# shock.net
KiCad netlist of a schematic drawn in Altium Designer
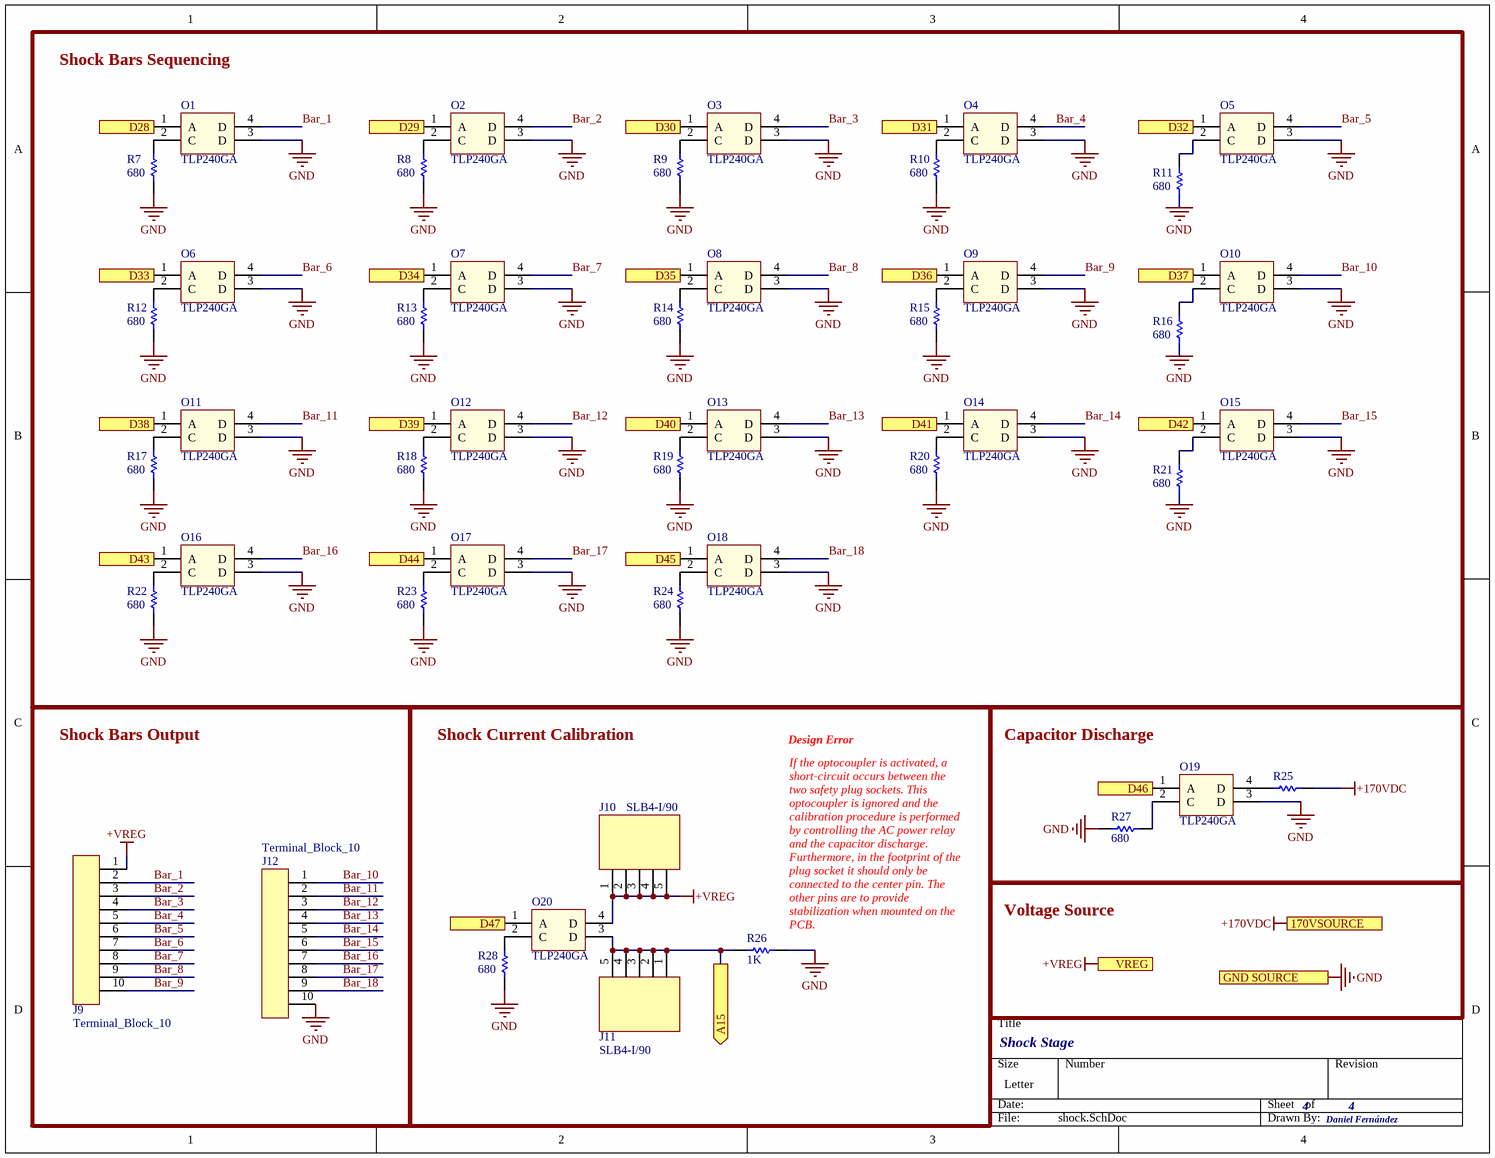
[diagram p0: shock.SchDoc]

(export (version "E")
  (design (tool "Eeschema 10.0.6"))
  (components
    (comp (ref "J9")
      (value "Terminal_Block_10")
      (footprint "Terminal_Block_10")
      (libsource (lib "Components_Schematics") (part "Terminal_Block_10"))
    )
    (comp (ref "J10") (value "SLB4-I/90") (footprint "SLB4-I/90") (libsource (lib "") (part "SLB4-I/90_1")))
    (comp (ref "J11")
      (value "SLB4-I/90")
      (footprint "SLB4-I/90")
      (libsource (lib "Components_Schematics") (part "SLB4-I/90"))
    )
    (comp (ref "J12")
      (value "Terminal_Block_10")
      (footprint "Terminal_Block_10")
      (libsource (lib "Components_Schematics") (part "Terminal_Block_10"))
    )
    (comp (ref "O1")
      (value "TLP240GA")
      (footprint "TLP240GA")
      (description "Photorelay")
      (libsource (lib "Components_Schematics") (part "TLP240GA"))
    )
    (comp (ref "O2")
      (value "TLP240GA")
      (footprint "TLP240GA")
      (description "Photorelay")
      (libsource (lib "Components_Schematics") (part "TLP240GA"))
    )
    (comp (ref "O3")
      (value "TLP240GA")
      (footprint "TLP240GA")
      (description "Photorelay")
      (libsource (lib "Components_Schematics") (part "TLP240GA"))
    )
    (comp (ref "O4")
      (value "TLP240GA")
      (footprint "TLP240GA")
      (description "Photorelay")
      (libsource (lib "Components_Schematics") (part "TLP240GA"))
    )
    (comp (ref "O5")
      (value "TLP240GA")
      (footprint "TLP240GA")
      (description "Photorelay")
      (libsource (lib "Components_Schematics") (part "TLP240GA"))
    )
    (comp (ref "O6")
      (value "TLP240GA")
      (footprint "TLP240GA")
      (description "Photorelay")
      (libsource (lib "Components_Schematics") (part "TLP240GA"))
    )
    (comp (ref "O7")
      (value "TLP240GA")
      (footprint "TLP240GA")
      (description "Photorelay")
      (libsource (lib "Components_Schematics") (part "TLP240GA"))
    )
    (comp (ref "O8")
      (value "TLP240GA")
      (footprint "TLP240GA")
      (description "Photorelay")
      (libsource (lib "Components_Schematics") (part "TLP240GA"))
    )
    (comp (ref "O9")
      (value "TLP240GA")
      (footprint "TLP240GA")
      (description "Photorelay")
      (libsource (lib "Components_Schematics") (part "TLP240GA"))
    )
    (comp (ref "O10")
      (value "TLP240GA")
      (footprint "TLP240GA")
      (description "Photorelay")
      (libsource (lib "Components_Schematics") (part "TLP240GA"))
    )
    (comp (ref "O11")
      (value "TLP240GA")
      (footprint "TLP240GA")
      (description "Photorelay")
      (libsource (lib "Components_Schematics") (part "TLP240GA"))
    )
    (comp (ref "O12")
      (value "TLP240GA")
      (footprint "TLP240GA")
      (description "Photorelay")
      (libsource (lib "Components_Schematics") (part "TLP240GA"))
    )
    (comp (ref "O13")
      (value "TLP240GA")
      (footprint "TLP240GA")
      (description "Photorelay")
      (libsource (lib "Components_Schematics") (part "TLP240GA"))
    )
    (comp (ref "O14")
      (value "TLP240GA")
      (footprint "TLP240GA")
      (description "Photorelay")
      (libsource (lib "Components_Schematics") (part "TLP240GA"))
    )
    (comp (ref "O15")
      (value "TLP240GA")
      (footprint "TLP240GA")
      (description "Photorelay")
      (libsource (lib "Components_Schematics") (part "TLP240GA"))
    )
    (comp (ref "O16")
      (value "TLP240GA")
      (footprint "TLP240GA")
      (description "Photorelay")
      (libsource (lib "Components_Schematics") (part "TLP240GA"))
    )
    (comp (ref "O17")
      (value "TLP240GA")
      (footprint "TLP240GA")
      (description "Photorelay")
      (libsource (lib "Components_Schematics") (part "TLP240GA"))
    )
    (comp (ref "O18")
      (value "TLP240GA")
      (footprint "TLP240GA")
      (description "Photorelay")
      (libsource (lib "Components_Schematics") (part "TLP240GA"))
    )
    (comp (ref "O19")
      (value "TLP240GA")
      (footprint "TLP240GA")
      (description "Photorelay")
      (libsource (lib "Components_Schematics") (part "TLP240GA"))
    )
    (comp (ref "O20")
      (value "TLP240GA")
      (footprint "TLP240GA")
      (description "Photorelay")
      (libsource (lib "Components_Schematics") (part "TLP240GA"))
    )
    (comp (ref "R7")
      (value "680")
      (footprint "RESISTOR")
      (description "Resistor_Axial")
      (fields (field (name "PUBLISHER") "Altium Limited"))
      (libsource (lib "PERCRO_schematic") (part "Resistor_Axial"))
    )
    (comp (ref "R8")
      (value "680")
      (footprint "RESISTOR")
      (description "Resistor_Axial")
      (fields (field (name "PUBLISHER") "Altium Limited"))
      (libsource (lib "PERCRO_schematic") (part "Resistor_Axial"))
    )
    (comp (ref "R9")
      (value "680")
      (footprint "RESISTOR")
      (description "Resistor_Axial")
      (fields (field (name "PUBLISHER") "Altium Limited"))
      (libsource (lib "PERCRO_schematic") (part "Resistor_Axial"))
    )
    (comp (ref "R10")
      (value "680")
      (footprint "RESISTOR")
      (description "Resistor_Axial")
      (fields (field (name "PUBLISHER") "Altium Limited"))
      (libsource (lib "PERCRO_schematic") (part "Resistor_Axial"))
    )
    (comp (ref "R11")
      (value "680")
      (footprint "RESISTOR")
      (description "Resistor_Axial")
      (fields (field (name "PUBLISHER") "Altium Limited"))
      (libsource (lib "PERCRO_schematic") (part "Resistor_Axial"))
    )
    (comp (ref "R12")
      (value "680")
      (footprint "RESISTOR")
      (description "Resistor_Axial")
      (fields (field (name "PUBLISHER") "Altium Limited"))
      (libsource (lib "PERCRO_schematic") (part "Resistor_Axial"))
    )
    (comp (ref "R13")
      (value "680")
      (footprint "RESISTOR")
      (description "Resistor_Axial")
      (fields (field (name "PUBLISHER") "Altium Limited"))
      (libsource (lib "PERCRO_schematic") (part "Resistor_Axial"))
    )
    (comp (ref "R14")
      (value "680")
      (footprint "RESISTOR")
      (description "Resistor_Axial")
      (fields (field (name "PUBLISHER") "Altium Limited"))
      (libsource (lib "PERCRO_schematic") (part "Resistor_Axial"))
    )
    (comp (ref "R15")
      (value "680")
      (footprint "RESISTOR")
      (description "Resistor_Axial")
      (fields (field (name "PUBLISHER") "Altium Limited"))
      (libsource (lib "PERCRO_schematic") (part "Resistor_Axial"))
    )
    (comp (ref "R16")
      (value "680")
      (footprint "RESISTOR")
      (description "Resistor_Axial")
      (fields (field (name "PUBLISHER") "Altium Limited"))
      (libsource (lib "PERCRO_schematic") (part "Resistor_Axial"))
    )
    (comp (ref "R17")
      (value "680")
      (footprint "RESISTOR")
      (description "Resistor_Axial")
      (fields (field (name "PUBLISHER") "Altium Limited"))
      (libsource (lib "PERCRO_schematic") (part "Resistor_Axial"))
    )
    (comp (ref "R18")
      (value "680")
      (footprint "RESISTOR")
      (description "Resistor_Axial")
      (fields (field (name "PUBLISHER") "Altium Limited"))
      (libsource (lib "PERCRO_schematic") (part "Resistor_Axial"))
    )
    (comp (ref "R19")
      (value "680")
      (footprint "RESISTOR")
      (description "Resistor_Axial")
      (fields (field (name "PUBLISHER") "Altium Limited"))
      (libsource (lib "PERCRO_schematic") (part "Resistor_Axial"))
    )
    (comp (ref "R20")
      (value "680")
      (footprint "RESISTOR")
      (description "Resistor_Axial")
      (fields (field (name "PUBLISHER") "Altium Limited"))
      (libsource (lib "PERCRO_schematic") (part "Resistor_Axial"))
    )
    (comp (ref "R21")
      (value "680")
      (footprint "RESISTOR")
      (description "Resistor_Axial")
      (fields (field (name "PUBLISHER") "Altium Limited"))
      (libsource (lib "PERCRO_schematic") (part "Resistor_Axial"))
    )
    (comp (ref "R22")
      (value "680")
      (footprint "RESISTOR")
      (description "Resistor_Axial")
      (fields (field (name "PUBLISHER") "Altium Limited"))
      (libsource (lib "PERCRO_schematic") (part "Resistor_Axial"))
    )
    (comp (ref "R23")
      (value "680")
      (footprint "RESISTOR")
      (description "Resistor_Axial")
      (fields (field (name "PUBLISHER") "Altium Limited"))
      (libsource (lib "PERCRO_schematic") (part "Resistor_Axial"))
    )
    (comp (ref "R24")
      (value "680")
      (footprint "RESISTOR")
      (description "Resistor_Axial")
      (fields (field (name "PUBLISHER") "Altium Limited"))
      (libsource (lib "PERCRO_schematic") (part "Resistor_Axial"))
    )
    (comp (ref "R25")
      (value "Ceramic Resistor")
      (footprint "AXIAL_CERAMIC_RESISTOR")
      (libsource (lib "Components_Schematics") (part "AXIAL_CERAMIC_RESISTOR"))
    )
    (comp (ref "R26")
      (value "1K")
      (footprint "RESISTOR")
      (description "Resistor_Axial")
      (fields (field (name "PUBLISHER") "Altium Limited"))
      (libsource (lib "PERCRO_schematic") (part "Resistor_Axial"))
    )
    (comp (ref "R27")
      (value "680")
      (footprint "RESISTOR")
      (description "Resistor_Axial")
      (fields (field (name "PUBLISHER") "Altium Limited"))
      (libsource (lib "PERCRO_schematic") (part "Resistor_Axial"))
    )
    (comp (ref "R28")
      (value "680")
      (footprint "RESISTOR")
      (description "Resistor_Axial")
      (fields (field (name "PUBLISHER") "Altium Limited"))
      (libsource (lib "PERCRO_schematic") (part "Resistor_Axial"))
    )
  )
  (nets
    (net (code "1") (name "+170VDC") (class "Default")
      (node (ref "R25") (pin "2") (pinfunction "2_2") (pintype "passive"))
    )
    (net (code "2") (name "+VREG") (class "Default")
      (node (ref "J10") (pin "1") (pinfunction "1_1") (pintype "passive"))
      (node (ref "J10") (pin "2") (pinfunction "Vin_2") (pintype "passive"))
      (node (ref "J10") (pin "3") (pinfunction "Vin_3") (pintype "passive"))
      (node (ref "J10") (pin "4") (pinfunction "Vin_4") (pintype "passive"))
      (node (ref "J10") (pin "5") (pinfunction "Vin_5") (pintype "passive"))
      (node (ref "J9") (pin "1") (pinfunction "1_1") (pintype "passive"))
      (node (ref "O20") (pin "4") (pinfunction "D_4") (pintype "passive"))
    )
    (net (code "3") (name "/A15") (class "Default")
      (node (ref "J11") (pin "1") (pinfunction "1_1") (pintype "passive"))
      (node (ref "J11") (pin "2") (pinfunction "Vin_2") (pintype "passive"))
      (node (ref "J11") (pin "3") (pinfunction "Vin_3") (pintype "passive"))
      (node (ref "J11") (pin "4") (pinfunction "Vin_4") (pintype "passive"))
      (node (ref "J11") (pin "5") (pinfunction "Vin_5") (pintype "passive"))
      (node (ref "O20") (pin "3") (pinfunction "D_3") (pintype "passive"))
      (node (ref "R26") (pin "1") (pinfunction "1_1") (pintype "passive"))
    )
    (net (code "4") (name "/Bar_1") (class "Default")
      (node (ref "J9") (pin "2") (pinfunction "2_2") (pintype "passive"))
      (node (ref "O1") (pin "4") (pinfunction "D_4") (pintype "passive"))
    )
    (net (code "5") (name "/Bar_2") (class "Default")
      (node (ref "J9") (pin "3") (pinfunction "3_3") (pintype "passive"))
      (node (ref "O2") (pin "4") (pinfunction "D_4") (pintype "passive"))
    )
    (net (code "6") (name "/Bar_3") (class "Default")
      (node (ref "J9") (pin "4") (pinfunction "4_4") (pintype "passive"))
      (node (ref "O3") (pin "4") (pinfunction "D_4") (pintype "passive"))
    )
    (net (code "7") (name "/Bar_4") (class "Default")
      (node (ref "J9") (pin "5") (pinfunction "5_5") (pintype "passive"))
      (node (ref "O4") (pin "4") (pinfunction "D_4") (pintype "passive"))
    )
    (net (code "8") (name "/Bar_5") (class "Default")
      (node (ref "J9") (pin "6") (pinfunction "6_6") (pintype "passive"))
      (node (ref "O5") (pin "4") (pinfunction "D_4") (pintype "passive"))
    )
    (net (code "9") (name "/Bar_6") (class "Default")
      (node (ref "J9") (pin "7") (pinfunction "7_7") (pintype "passive"))
      (node (ref "O6") (pin "4") (pinfunction "D_4") (pintype "passive"))
    )
    (net (code "10") (name "/Bar_7") (class "Default")
      (node (ref "J9") (pin "8") (pinfunction "8_8") (pintype "passive"))
      (node (ref "O7") (pin "4") (pinfunction "D_4") (pintype "passive"))
    )
    (net (code "11") (name "/Bar_8") (class "Default")
      (node (ref "J9") (pin "9") (pinfunction "9_9") (pintype "passive"))
      (node (ref "O8") (pin "4") (pinfunction "D_4") (pintype "passive"))
    )
    (net (code "12") (name "/Bar_9") (class "Default")
      (node (ref "J9") (pin "10") (pinfunction "10_10") (pintype "passive"))
      (node (ref "O9") (pin "4") (pinfunction "D_4") (pintype "passive"))
    )
    (net (code "13") (name "/Bar_10") (class "Default")
      (node (ref "J12") (pin "1") (pinfunction "1_1") (pintype "passive"))
      (node (ref "O10") (pin "4") (pinfunction "D_4") (pintype "passive"))
    )
    (net (code "14") (name "/Bar_11") (class "Default")
      (node (ref "J12") (pin "2") (pinfunction "2_2") (pintype "passive"))
      (node (ref "O11") (pin "4") (pinfunction "D_4") (pintype "passive"))
    )
    (net (code "15") (name "/Bar_12") (class "Default")
      (node (ref "J12") (pin "3") (pinfunction "3_3") (pintype "passive"))
      (node (ref "O12") (pin "4") (pinfunction "D_4") (pintype "passive"))
    )
    (net (code "16") (name "/Bar_13") (class "Default")
      (node (ref "J12") (pin "4") (pinfunction "4_4") (pintype "passive"))
      (node (ref "O13") (pin "4") (pinfunction "D_4") (pintype "passive"))
    )
    (net (code "17") (name "/Bar_14") (class "Default")
      (node (ref "J12") (pin "5") (pinfunction "5_5") (pintype "passive"))
      (node (ref "O14") (pin "4") (pinfunction "D_4") (pintype "passive"))
    )
    (net (code "18") (name "/Bar_15") (class "Default")
      (node (ref "J12") (pin "6") (pinfunction "6_6") (pintype "passive"))
      (node (ref "O15") (pin "4") (pinfunction "D_4") (pintype "passive"))
    )
    (net (code "19") (name "/Bar_16") (class "Default")
      (node (ref "J12") (pin "7") (pinfunction "7_7") (pintype "passive"))
      (node (ref "O16") (pin "4") (pinfunction "D_4") (pintype "passive"))
    )
    (net (code "20") (name "/Bar_17") (class "Default")
      (node (ref "J12") (pin "8") (pinfunction "8_8") (pintype "passive"))
      (node (ref "O17") (pin "4") (pinfunction "D_4") (pintype "passive"))
    )
    (net (code "21") (name "/Bar_18") (class "Default")
      (node (ref "J12") (pin "9") (pinfunction "9_9") (pintype "passive"))
      (node (ref "O18") (pin "4") (pinfunction "D_4") (pintype "passive"))
    )
    (net (code "22") (name "/D28") (class "Default")
      (node (ref "O1") (pin "1") (pinfunction "A_1") (pintype "passive"))
    )
    (net (code "23") (name "/D29") (class "Default")
      (node (ref "O2") (pin "1") (pinfunction "A_1") (pintype "passive"))
    )
    (net (code "24") (name "/D30") (class "Default")
      (node (ref "O3") (pin "1") (pinfunction "A_1") (pintype "passive"))
    )
    (net (code "25") (name "/D31") (class "Default")
      (node (ref "O4") (pin "1") (pinfunction "A_1") (pintype "passive"))
    )
    (net (code "26") (name "/D32") (class "Default")
      (node (ref "O5") (pin "1") (pinfunction "A_1") (pintype "passive"))
    )
    (net (code "27") (name "/D33") (class "Default")
      (node (ref "O6") (pin "1") (pinfunction "A_1") (pintype "passive"))
    )
    (net (code "28") (name "/D34") (class "Default")
      (node (ref "O7") (pin "1") (pinfunction "A_1") (pintype "passive"))
    )
    (net (code "29") (name "/D35") (class "Default")
      (node (ref "O8") (pin "1") (pinfunction "A_1") (pintype "passive"))
    )
    (net (code "30") (name "/D36") (class "Default")
      (node (ref "O9") (pin "1") (pinfunction "A_1") (pintype "passive"))
    )
    (net (code "31") (name "/D37") (class "Default")
      (node (ref "O10") (pin "1") (pinfunction "A_1") (pintype "passive"))
    )
    (net (code "32") (name "/D38") (class "Default")
      (node (ref "O11") (pin "1") (pinfunction "A_1") (pintype "passive"))
    )
    (net (code "33") (name "/D39") (class "Default")
      (node (ref "O12") (pin "1") (pinfunction "A_1") (pintype "passive"))
    )
    (net (code "34") (name "/D40") (class "Default")
      (node (ref "O13") (pin "1") (pinfunction "A_1") (pintype "passive"))
    )
    (net (code "35") (name "/D41") (class "Default")
      (node (ref "O14") (pin "1") (pinfunction "A_1") (pintype "passive"))
    )
    (net (code "36") (name "/D42") (class "Default")
      (node (ref "O15") (pin "1") (pinfunction "A_1") (pintype "passive"))
    )
    (net (code "37") (name "/D43") (class "Default")
      (node (ref "O16") (pin "1") (pinfunction "A_1") (pintype "passive"))
    )
    (net (code "38") (name "/D44") (class "Default")
      (node (ref "O17") (pin "1") (pinfunction "A_1") (pintype "passive"))
    )
    (net (code "39") (name "/D45") (class "Default")
      (node (ref "O18") (pin "1") (pinfunction "A_1") (pintype "passive"))
    )
    (net (code "40") (name "/D46") (class "Default")
      (node (ref "O19") (pin "1") (pinfunction "A_1") (pintype "passive"))
    )
    (net (code "41") (name "/D47") (class "Default")
      (node (ref "O20") (pin "1") (pinfunction "A_1") (pintype "passive"))
    )
    (net (code "42") (name "GND") (class "Default")
      (node (ref "J12") (pin "10") (pinfunction "10_10") (pintype "passive"))
      (node (ref "O1") (pin "3") (pinfunction "D_3") (pintype "passive"))
      (node (ref "O10") (pin "3") (pinfunction "D_3") (pintype "passive"))
      (node (ref "O11") (pin "3") (pinfunction "D_3") (pintype "passive"))
      (node (ref "O12") (pin "3") (pinfunction "D_3") (pintype "passive"))
      (node (ref "O13") (pin "3") (pinfunction "D_3") (pintype "passive"))
      (node (ref "O14") (pin "3") (pinfunction "D_3") (pintype "passive"))
      (node (ref "O15") (pin "3") (pinfunction "D_3") (pintype "passive"))
      (node (ref "O16") (pin "3") (pinfunction "D_3") (pintype "passive"))
      (node (ref "O17") (pin "3") (pinfunction "D_3") (pintype "passive"))
      (node (ref "O18") (pin "3") (pinfunction "D_3") (pintype "passive"))
      (node (ref "O19") (pin "3") (pinfunction "D_3") (pintype "passive"))
      (node (ref "O2") (pin "3") (pinfunction "D_3") (pintype "passive"))
      (node (ref "O3") (pin "3") (pinfunction "D_3") (pintype "passive"))
      (node (ref "O4") (pin "3") (pinfunction "D_3") (pintype "passive"))
      (node (ref "O5") (pin "3") (pinfunction "D_3") (pintype "passive"))
      (node (ref "O6") (pin "3") (pinfunction "D_3") (pintype "passive"))
      (node (ref "O7") (pin "3") (pinfunction "D_3") (pintype "passive"))
      (node (ref "O8") (pin "3") (pinfunction "D_3") (pintype "passive"))
      (node (ref "O9") (pin "3") (pinfunction "D_3") (pintype "passive"))
      (node (ref "R10") (pin "1") (pinfunction "1_1") (pintype "passive"))
      (node (ref "R11") (pin "1") (pinfunction "1_1") (pintype "passive"))
      (node (ref "R12") (pin "1") (pinfunction "1_1") (pintype "passive"))
      (node (ref "R13") (pin "1") (pinfunction "1_1") (pintype "passive"))
      (node (ref "R14") (pin "1") (pinfunction "1_1") (pintype "passive"))
      (node (ref "R15") (pin "1") (pinfunction "1_1") (pintype "passive"))
      (node (ref "R16") (pin "1") (pinfunction "1_1") (pintype "passive"))
      (node (ref "R17") (pin "1") (pinfunction "1_1") (pintype "passive"))
      (node (ref "R18") (pin "1") (pinfunction "1_1") (pintype "passive"))
      (node (ref "R19") (pin "1") (pinfunction "1_1") (pintype "passive"))
      (node (ref "R20") (pin "1") (pinfunction "1_1") (pintype "passive"))
      (node (ref "R21") (pin "1") (pinfunction "1_1") (pintype "passive"))
      (node (ref "R22") (pin "1") (pinfunction "1_1") (pintype "passive"))
      (node (ref "R23") (pin "1") (pinfunction "1_1") (pintype "passive"))
      (node (ref "R24") (pin "1") (pinfunction "1_1") (pintype "passive"))
      (node (ref "R26") (pin "2") (pinfunction "2_2") (pintype "passive"))
      (node (ref "R27") (pin "1") (pinfunction "1_1") (pintype "passive"))
      (node (ref "R28") (pin "1") (pinfunction "1_1") (pintype "passive"))
      (node (ref "R7") (pin "1") (pinfunction "1_1") (pintype "passive"))
      (node (ref "R8") (pin "1") (pinfunction "1_1") (pintype "passive"))
      (node (ref "R9") (pin "1") (pinfunction "1_1") (pintype "passive"))
    )
    (net (code "43") (name "Net-(O1-C)") (class "Default")
      (node (ref "O1") (pin "2") (pinfunction "C_2") (pintype "passive"))
      (node (ref "R7") (pin "2") (pinfunction "2_2") (pintype "passive"))
    )
    (net (code "44") (name "Net-(O2-C)") (class "Default")
      (node (ref "O2") (pin "2") (pinfunction "C_2") (pintype "passive"))
      (node (ref "R8") (pin "2") (pinfunction "2_2") (pintype "passive"))
    )
    (net (code "45") (name "Net-(O3-C)") (class "Default")
      (node (ref "O3") (pin "2") (pinfunction "C_2") (pintype "passive"))
      (node (ref "R9") (pin "2") (pinfunction "2_2") (pintype "passive"))
    )
    (net (code "46") (name "Net-(O4-C)") (class "Default")
      (node (ref "O4") (pin "2") (pinfunction "C_2") (pintype "passive"))
      (node (ref "R10") (pin "2") (pinfunction "2_2") (pintype "passive"))
    )
    (net (code "47") (name "Net-(O5-C)") (class "Default")
      (node (ref "O5") (pin "2") (pinfunction "C_2") (pintype "passive"))
      (node (ref "R11") (pin "2") (pinfunction "2_2") (pintype "passive"))
    )
    (net (code "48") (name "Net-(O6-C)") (class "Default")
      (node (ref "O6") (pin "2") (pinfunction "C_2") (pintype "passive"))
      (node (ref "R12") (pin "2") (pinfunction "2_2") (pintype "passive"))
    )
    (net (code "49") (name "Net-(O7-C)") (class "Default")
      (node (ref "O7") (pin "2") (pinfunction "C_2") (pintype "passive"))
      (node (ref "R13") (pin "2") (pinfunction "2_2") (pintype "passive"))
    )
    (net (code "50") (name "Net-(O8-C)") (class "Default")
      (node (ref "O8") (pin "2") (pinfunction "C_2") (pintype "passive"))
      (node (ref "R14") (pin "2") (pinfunction "2_2") (pintype "passive"))
    )
    (net (code "51") (name "Net-(O9-C)") (class "Default")
      (node (ref "O9") (pin "2") (pinfunction "C_2") (pintype "passive"))
      (node (ref "R15") (pin "2") (pinfunction "2_2") (pintype "passive"))
    )
    (net (code "52") (name "Net-(O10-C)") (class "Default")
      (node (ref "O10") (pin "2") (pinfunction "C_2") (pintype "passive"))
      (node (ref "R16") (pin "2") (pinfunction "2_2") (pintype "passive"))
    )
    (net (code "53") (name "Net-(O11-C)") (class "Default")
      (node (ref "O11") (pin "2") (pinfunction "C_2") (pintype "passive"))
      (node (ref "R17") (pin "2") (pinfunction "2_2") (pintype "passive"))
    )
    (net (code "54") (name "Net-(O12-C)") (class "Default")
      (node (ref "O12") (pin "2") (pinfunction "C_2") (pintype "passive"))
      (node (ref "R18") (pin "2") (pinfunction "2_2") (pintype "passive"))
    )
    (net (code "55") (name "Net-(O13-C)") (class "Default")
      (node (ref "O13") (pin "2") (pinfunction "C_2") (pintype "passive"))
      (node (ref "R19") (pin "2") (pinfunction "2_2") (pintype "passive"))
    )
    (net (code "56") (name "Net-(O14-C)") (class "Default")
      (node (ref "O14") (pin "2") (pinfunction "C_2") (pintype "passive"))
      (node (ref "R20") (pin "2") (pinfunction "2_2") (pintype "passive"))
    )
    (net (code "57") (name "Net-(O15-C)") (class "Default")
      (node (ref "O15") (pin "2") (pinfunction "C_2") (pintype "passive"))
      (node (ref "R21") (pin "2") (pinfunction "2_2") (pintype "passive"))
    )
    (net (code "58") (name "Net-(O16-C)") (class "Default")
      (node (ref "O16") (pin "2") (pinfunction "C_2") (pintype "passive"))
      (node (ref "R22") (pin "2") (pinfunction "2_2") (pintype "passive"))
    )
    (net (code "59") (name "Net-(O17-C)") (class "Default")
      (node (ref "O17") (pin "2") (pinfunction "C_2") (pintype "passive"))
      (node (ref "R23") (pin "2") (pinfunction "2_2") (pintype "passive"))
    )
    (net (code "60") (name "Net-(O18-C)") (class "Default")
      (node (ref "O18") (pin "2") (pinfunction "C_2") (pintype "passive"))
      (node (ref "R24") (pin "2") (pinfunction "2_2") (pintype "passive"))
    )
    (net (code "61") (name "Net-(O19-C)") (class "Default")
      (node (ref "O19") (pin "2") (pinfunction "C_2") (pintype "passive"))
      (node (ref "R27") (pin "2") (pinfunction "2_2") (pintype "passive"))
    )
    (net (code "62") (name "Net-(O19-D-Pad4)") (class "Default")
      (node (ref "O19") (pin "4") (pinfunction "D_4") (pintype "passive"))
      (node (ref "R25") (pin "1") (pinfunction "1_1") (pintype "passive"))
    )
    (net (code "63") (name "Net-(O20-C)") (class "Default")
      (node (ref "O20") (pin "2") (pinfunction "C_2") (pintype "passive"))
      (node (ref "R28") (pin "2") (pinfunction "2_2") (pintype "passive"))
    )
  )
)
